# EnvironmentMonitorV5_1.net
KiCad netlist of a schematic drawn in EAGLE
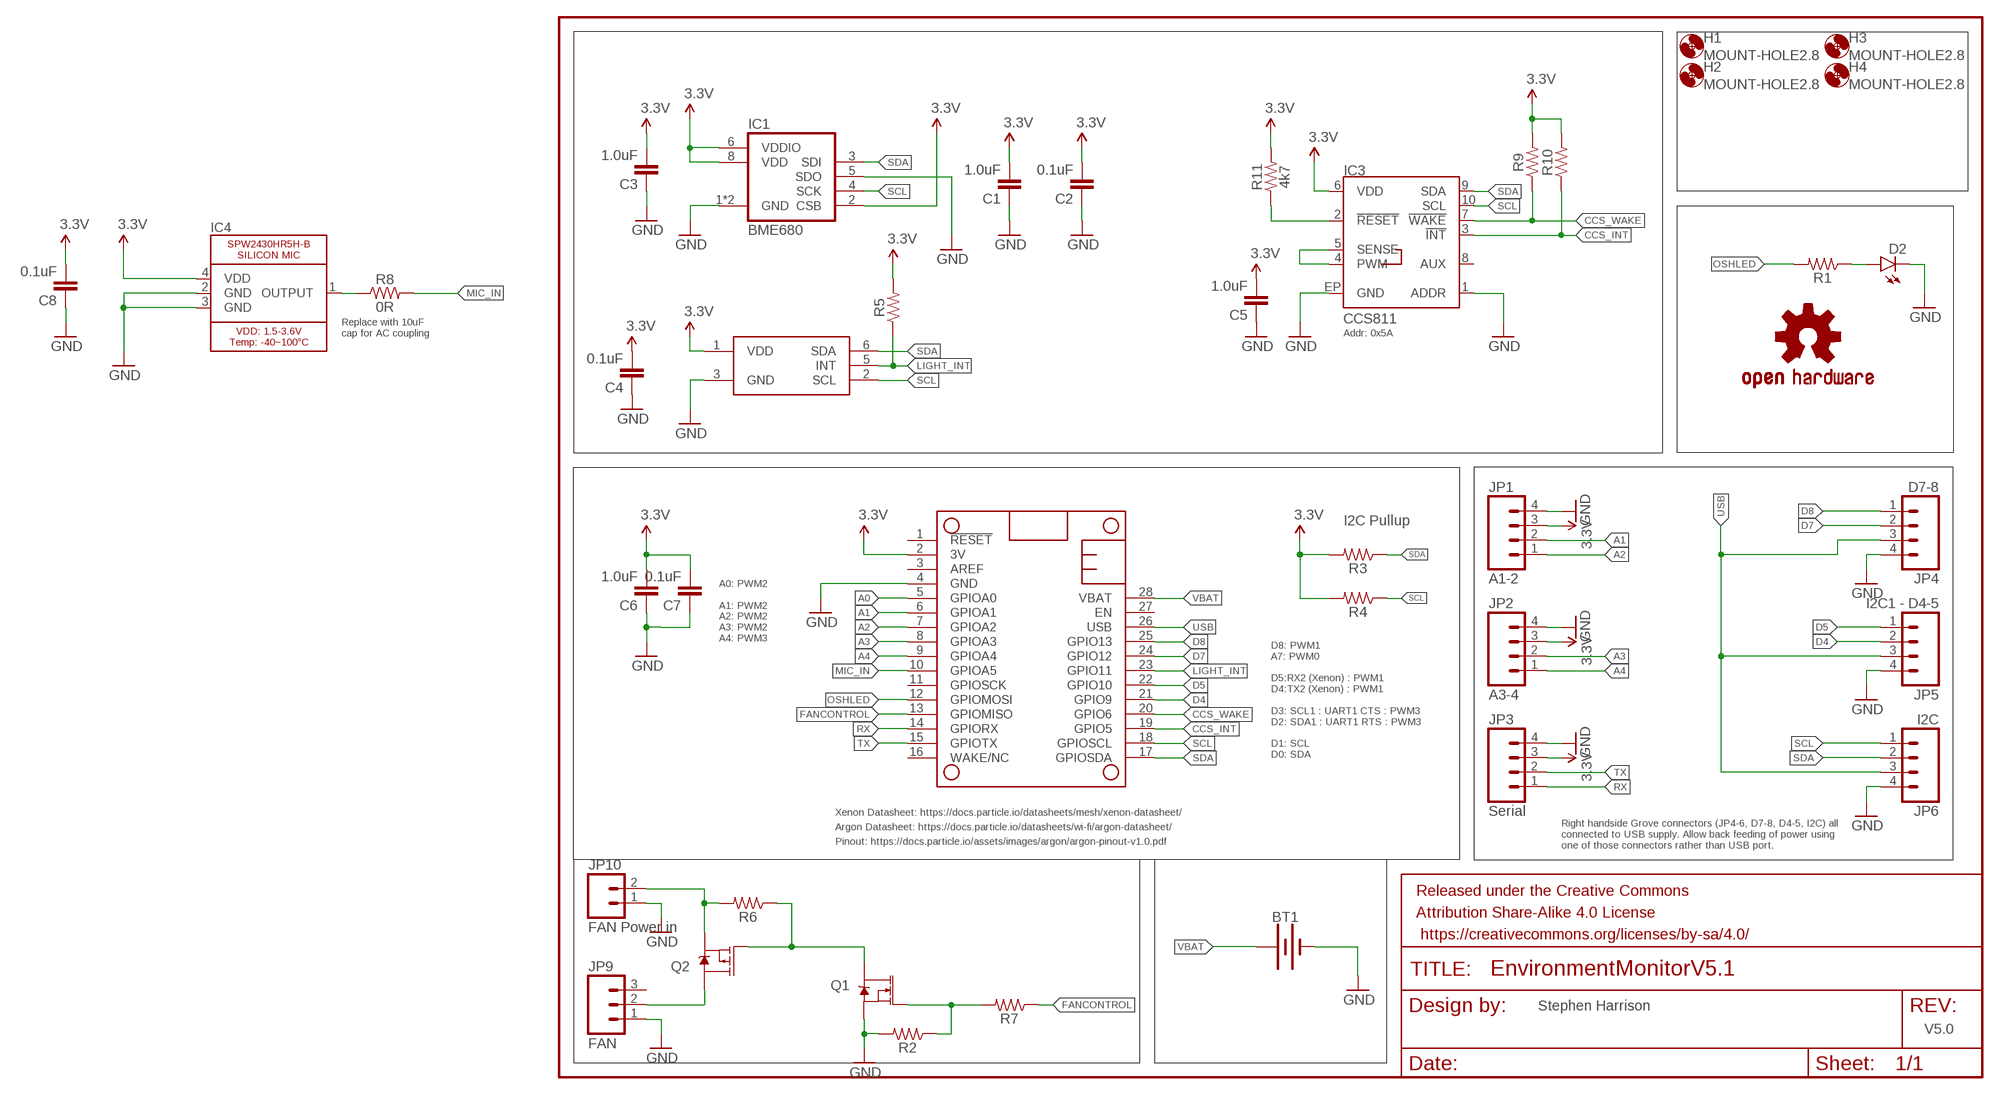
[diagram p0: schematic, sheet 1]

(export (version "E")
  (design (tool "Eeschema 10.0.6"))
  (components
    (comp (ref "BT1")
      (value "BATTERY-16340")
      (footprint "eagle-import:BATTERY_16340-HOLDER")
      (libsource (lib "eagle-import") (part "BATTERY-16340"))
    )
    (comp (ref "C1")
      (value "1.0uF")
      (footprint "eagle-import:0805-CAP")
      (libsource (lib "eagle-import") (part "1.0UF-25V-+80/-20(0805){dblquote}"))
    )
    (comp (ref "C2")
      (value "0.1uF")
      (footprint "eagle-import:0805-CAP")
      (libsource (lib "eagle-import") (part "1.0UF-25V-+80/-20(0805){dblquote}"))
    )
    (comp (ref "C3")
      (value "1.0uF")
      (footprint "eagle-import:0805-CAP")
      (libsource (lib "eagle-import") (part "1.0UF-25V-+80/-20(0805){dblquote}"))
    )
    (comp (ref "C4")
      (value "0.1uF")
      (footprint "eagle-import:0805-CAP")
      (libsource (lib "eagle-import") (part "1.0UF-25V-+80/-20(0805){dblquote}"))
    )
    (comp (ref "C5")
      (value "1.0uF")
      (footprint "eagle-import:0805-CAP")
      (libsource (lib "eagle-import") (part "1.0UF-25V-+80/-20(0805){dblquote}"))
    )
    (comp (ref "C6")
      (value "1.0uF")
      (footprint "eagle-import:0805-CAP")
      (libsource (lib "eagle-import") (part "1.0UF-25V-+80/-20(0805){dblquote}"))
    )
    (comp (ref "C7")
      (value "0.1uF")
      (footprint "eagle-import:0805-CAP")
      (libsource (lib "eagle-import") (part "1.0UF-25V-+80/-20(0805){dblquote}"))
    )
    (comp (ref "C8")
      (value "0.1uF")
      (footprint "eagle-import:0805-CAP")
      (libsource (lib "eagle-import") (part "1.0UF-25V-+80/-20(0805){dblquote}"))
    )
    (comp (ref "D2")
      (value "LED1206-BOTTOM")
      (footprint "eagle-import:LED-1206-BOTTOM")
      (libsource (lib "eagle-import") (part "LED1206-BOTTOM"))
    )
    (comp (ref "FRAME1")
      (value "FRAME-LETTER")
      (footprint "eagle-import:CREATIVE_COMMONS")
      (libsource (lib "eagle-import") (part "FRAME-LETTER"))
    )
    (comp (ref "H1")
      (value "MOUNT-HOLE2.8")
      (footprint "eagle-import:2,8")
      (libsource (lib "eagle-import") (part "MOUNT-HOLE2.8"))
    )
    (comp (ref "H2")
      (value "MOUNT-HOLE2.8")
      (footprint "eagle-import:2,8")
      (libsource (lib "eagle-import") (part "MOUNT-HOLE2.8"))
    )
    (comp (ref "H3")
      (value "MOUNT-HOLE2.8")
      (footprint "eagle-import:2,8")
      (libsource (lib "eagle-import") (part "MOUNT-HOLE2.8"))
    )
    (comp (ref "H4")
      (value "MOUNT-HOLE2.8")
      (footprint "eagle-import:2,8")
      (libsource (lib "eagle-import") (part "MOUNT-HOLE2.8"))
    )
    (comp (ref "IC1")
      (value "BME680")
      (footprint "eagle-import:BME680")
      (libsource (lib "eagle-import") (part "BME680"))
    )
    (comp (ref "IC2")
      (value "TCS3472")
      (footprint "eagle-import:FN-6")
      (libsource (lib "eagle-import") (part "TCS3472"))
    )
    (comp (ref "IC3")
      (value "CCS811")
      (footprint "eagle-import:LGA10")
      (libsource (lib "eagle-import") (part "CCS811"))
    )
    (comp (ref "IC4")
      (value "SPW2430HR5H-B")
      (footprint "eagle-import:SPW2430HR5H-B")
      (libsource (lib "eagle-import") (part "SPW2430HR5H-B"))
    )
    (comp (ref "IC5")
      (value "FEATHERWING_NODIM")
      (footprint "eagle-import:FEATHERWING_DIM")
      (libsource (lib "eagle-import") (part "FEATHERWING_NODIM"))
    )
    (comp (ref "JP1")
      (value "A1-2")
      (footprint "eagle-import:JST-4-PTH-VERT")
      (libsource (lib "eagle-import") (part "M04JST-PTH-VERT"))
    )
    (comp (ref "JP2")
      (value "A3-4")
      (footprint "eagle-import:JST-4-PTH-VERT")
      (libsource (lib "eagle-import") (part "M04JST-PTH-VERT"))
    )
    (comp (ref "JP3")
      (value "Serial")
      (footprint "eagle-import:JST-4-PTH-VERT")
      (libsource (lib "eagle-import") (part "M04JST-PTH-VERT"))
    )
    (comp (ref "JP4")
      (value "D7-8")
      (footprint "eagle-import:JST-4-PTH-VERT")
      (libsource (lib "eagle-import") (part "M04JST-PTH-VERT"))
    )
    (comp (ref "JP5")
      (value "I2C1 - D4-5")
      (footprint "eagle-import:JST-4-PTH-VERT")
      (libsource (lib "eagle-import") (part "M04JST-PTH-VERT"))
    )
    (comp (ref "JP6")
      (value "I2C")
      (footprint "eagle-import:JST-4-PTH-VERT")
      (libsource (lib "eagle-import") (part "M04JST-PTH-VERT"))
    )
    (comp (ref "JP9")
      (value "FAN")
      (footprint "eagle-import:MOLEX-1X3")
      (libsource (lib "eagle-import") (part "M03POLAR"))
    )
    (comp (ref "JP10")
      (value "FAN Power in")
      (footprint "eagle-import:MOLEX-1X2_LOCK")
      (libsource (lib "eagle-import") (part "M02POLAR_LOCK"))
    )
    (comp (ref "LOGO1")
      (value "OSHW-LOGOM")
      (footprint "eagle-import:OSHW-LOGO-M")
      (libsource (lib "eagle-import") (part "OSHW-LOGOM"))
    )
    (comp (ref "Q1")
      (value "220mA/50V/3.5Ω")
      (footprint "eagle-import:SOT23-3")
      (libsource (lib "eagle-import") (part "MOSFET-NCH-BSS138"))
    )
    (comp (ref "Q2")
      (value "4.3A/20V/54mΩ")
      (footprint "eagle-import:SOT23-3")
      (libsource (lib "eagle-import") (part "MOSFET_PCH-IRLML2244"))
    )
    (comp (ref "R1")
      (value "RESISTOR0805")
      (footprint "eagle-import:0805")
      (libsource (lib "eagle-import") (part "RESISTOR0805"))
    )
    (comp (ref "R2")
      (value "RESISTOR0805")
      (footprint "eagle-import:0805")
      (libsource (lib "eagle-import") (part "RESISTOR0805"))
    )
    (comp (ref "R3")
      (value "RESISTOR0805")
      (footprint "eagle-import:0805")
      (libsource (lib "eagle-import") (part "RESISTOR0805"))
    )
    (comp (ref "R4")
      (value "RESISTOR0805")
      (footprint "eagle-import:0805")
      (libsource (lib "eagle-import") (part "RESISTOR0805"))
    )
    (comp (ref "R5")
      (value "RESISTOR0805")
      (footprint "eagle-import:0805")
      (libsource (lib "eagle-import") (part "RESISTOR0805"))
    )
    (comp (ref "R6")
      (value "RESISTOR0805")
      (footprint "eagle-import:0805")
      (libsource (lib "eagle-import") (part "RESISTOR0805"))
    )
    (comp (ref "R7")
      (value "RESISTOR0805")
      (footprint "eagle-import:0805")
      (libsource (lib "eagle-import") (part "RESISTOR0805"))
    )
    (comp (ref "R8")
      (value "0R")
      (footprint "eagle-import:0805")
      (libsource (lib "eagle-import") (part "RESISTOR0805"))
    )
    (comp (ref "R9")
      (value "RESISTOR0805")
      (footprint "eagle-import:0805")
      (libsource (lib "eagle-import") (part "RESISTOR0805"))
    )
    (comp (ref "R10")
      (value "RESISTOR0805")
      (footprint "eagle-import:0805")
      (libsource (lib "eagle-import") (part "RESISTOR0805"))
    )
    (comp (ref "R11")
      (value "4k7")
      (footprint "eagle-import:0805")
      (libsource (lib "eagle-import") (part "RESISTOR0805"))
    )
  )
  (nets
    (net (code "1") (name "3.3V") (class "Default")
      (node (ref "C1") (pin "2") (pinfunction "2_2") (pintype "passive"))
      (node (ref "C2") (pin "2") (pinfunction "2_2") (pintype "passive"))
      (node (ref "C3") (pin "2") (pinfunction "2_2") (pintype "passive"))
      (node (ref "C4") (pin "2") (pinfunction "2_2") (pintype "passive"))
      (node (ref "C5") (pin "2") (pinfunction "2_2") (pintype "passive"))
      (node (ref "C6") (pin "2") (pinfunction "2_2") (pintype "passive"))
      (node (ref "C7") (pin "2") (pinfunction "2_2") (pintype "passive"))
      (node (ref "C8") (pin "2") (pinfunction "2_2") (pintype "passive"))
      (node (ref "IC1") (pin "2") (pinfunction "CSB_2") (pintype "input"))
      (node (ref "IC1") (pin "6") (pinfunction "VDDIO_6") (pintype "power_in"))
      (node (ref "IC1") (pin "8") (pinfunction "VDD_8") (pintype "power_in"))
      (node (ref "IC2") (pin "1") (pinfunction "VDD_1") (pintype "bidirectional"))
      (node (ref "IC3") (pin "6") (pinfunction "VDD_6") (pintype "bidirectional"))
      (node (ref "IC4") (pin "4") (pinfunction "VDD_4") (pintype "power_in"))
      (node (ref "IC5") (pin "2") (pinfunction "3V_2") (pintype "power_in"))
      (node (ref "JP1") (pin "3") (pinfunction "3_3") (pintype "passive"))
      (node (ref "JP2") (pin "3") (pinfunction "3_3") (pintype "passive"))
      (node (ref "JP3") (pin "3") (pinfunction "3_3") (pintype "passive"))
      (node (ref "R10") (pin "2") (pinfunction "2_2") (pintype "passive"))
      (node (ref "R11") (pin "2") (pinfunction "2_2") (pintype "passive"))
      (node (ref "R3") (pin "2") (pinfunction "2_2") (pintype "passive"))
      (node (ref "R4") (pin "2") (pinfunction "2_2") (pintype "passive"))
      (node (ref "R5") (pin "2") (pinfunction "2_2") (pintype "passive"))
      (node (ref "R9") (pin "2") (pinfunction "2_2") (pintype "passive"))
    )
    (net (code "2") (name "A0") (class "Default")
      (node (ref "IC5") (pin "5") (pinfunction "GPIOA0_5") (pintype "bidirectional"))
    )
    (net (code "3") (name "A1") (class "Default")
      (node (ref "IC5") (pin "6") (pinfunction "GPIOA1_6") (pintype "bidirectional"))
      (node (ref "JP1") (pin "2") (pinfunction "2_2") (pintype "passive"))
    )
    (net (code "4") (name "A2") (class "Default")
      (node (ref "IC5") (pin "7") (pinfunction "GPIOA2_7") (pintype "bidirectional"))
      (node (ref "JP1") (pin "1") (pinfunction "1_1") (pintype "passive"))
    )
    (net (code "5") (name "A3") (class "Default")
      (node (ref "IC5") (pin "8") (pinfunction "GPIOA3_8") (pintype "bidirectional"))
      (node (ref "JP2") (pin "2") (pinfunction "2_2") (pintype "passive"))
    )
    (net (code "6") (name "A4") (class "Default")
      (node (ref "IC5") (pin "9") (pinfunction "GPIOA4_9") (pintype "bidirectional"))
      (node (ref "JP2") (pin "1") (pinfunction "1_1") (pintype "passive"))
    )
    (net (code "7") (name "CCS_INT") (class "Default")
      (node (ref "IC3") (pin "3") (pinfunction "~{INT}_3") (pintype "bidirectional"))
      (node (ref "IC5") (pin "19") (pinfunction "GPIO5_19") (pintype "bidirectional"))
      (node (ref "R10") (pin "1") (pinfunction "1_1") (pintype "passive"))
    )
    (net (code "8") (name "CCS_WAKE") (class "Default")
      (node (ref "IC3") (pin "7") (pinfunction "~{WAKE}_7") (pintype "bidirectional"))
      (node (ref "IC5") (pin "20") (pinfunction "GPIO6_20") (pintype "bidirectional"))
      (node (ref "R9") (pin "1") (pinfunction "1_1") (pintype "passive"))
    )
    (net (code "9") (name "D4") (class "Default")
      (node (ref "IC5") (pin "21") (pinfunction "GPIO9_21") (pintype "bidirectional"))
      (node (ref "JP5") (pin "2") (pinfunction "2_2") (pintype "passive"))
    )
    (net (code "10") (name "D5") (class "Default")
      (node (ref "IC5") (pin "22") (pinfunction "GPIO10_22") (pintype "bidirectional"))
      (node (ref "JP5") (pin "1") (pinfunction "1_1") (pintype "passive"))
    )
    (net (code "11") (name "D7") (class "Default")
      (node (ref "IC5") (pin "24") (pinfunction "GPIO12_24") (pintype "bidirectional"))
      (node (ref "JP4") (pin "2") (pinfunction "2_2") (pintype "passive"))
    )
    (net (code "12") (name "D8") (class "Default")
      (node (ref "IC5") (pin "25") (pinfunction "GPIO13_25") (pintype "bidirectional"))
      (node (ref "JP4") (pin "1") (pinfunction "1_1") (pintype "passive"))
    )
    (net (code "13") (name "FANCONTROL") (class "Default")
      (node (ref "IC5") (pin "13") (pinfunction "GPIOMISO_13") (pintype "bidirectional"))
      (node (ref "R7") (pin "1") (pinfunction "1_1") (pintype "passive"))
    )
    (net (code "14") (name "GND") (class "Default")
      (node (ref "BT1") (pin "P$2") (pinfunction "-_P$2") (pintype "power_in"))
      (node (ref "C1") (pin "1") (pinfunction "1_1") (pintype "passive"))
      (node (ref "C2") (pin "1") (pinfunction "1_1") (pintype "passive"))
      (node (ref "C3") (pin "1") (pinfunction "1_1") (pintype "passive"))
      (node (ref "C4") (pin "1") (pinfunction "1_1") (pintype "passive"))
      (node (ref "C5") (pin "1") (pinfunction "1_1") (pintype "passive"))
      (node (ref "C6") (pin "1") (pinfunction "1_1") (pintype "passive"))
      (node (ref "C7") (pin "1") (pinfunction "1_1") (pintype "passive"))
      (node (ref "C8") (pin "1") (pinfunction "1_1") (pintype "passive"))
      (node (ref "D2") (pin "C") (pinfunction "C_C") (pintype "passive"))
      (node (ref "IC1") (pin "1") (pinfunction "GND_1") (pintype "power_in"))
      (node (ref "IC1") (pin "5") (pinfunction "SDO_5") (pintype "output"))
      (node (ref "IC1") (pin "7") (pinfunction "GND_7") (pintype "power_in"))
      (node (ref "IC2") (pin "3") (pinfunction "GND_3") (pintype "bidirectional"))
      (node (ref "IC3") (pin "1") (pinfunction "ADDR_1") (pintype "bidirectional"))
      (node (ref "IC3") (pin "EP") (pinfunction "GND_EP") (pintype "bidirectional"))
      (node (ref "IC4") (pin "2") (pinfunction "GND_2") (pintype "power_in"))
      (node (ref "IC4") (pin "3") (pinfunction "GND_3") (pintype "power_in"))
      (node (ref "IC5") (pin "4") (pinfunction "GND_4") (pintype "power_in"))
      (node (ref "JP1") (pin "4") (pinfunction "4_4") (pintype "passive"))
      (node (ref "JP10") (pin "1") (pinfunction "1_1") (pintype "passive"))
      (node (ref "JP2") (pin "4") (pinfunction "4_4") (pintype "passive"))
      (node (ref "JP3") (pin "4") (pinfunction "4_4") (pintype "passive"))
      (node (ref "JP4") (pin "4") (pinfunction "4_4") (pintype "passive"))
      (node (ref "JP5") (pin "4") (pinfunction "4_4") (pintype "passive"))
      (node (ref "JP6") (pin "4") (pinfunction "4_4") (pintype "passive"))
      (node (ref "JP9") (pin "1") (pinfunction "1_1") (pintype "passive"))
      (node (ref "Q1") (pin "2") (pinfunction "S_2") (pintype "bidirectional"))
      (node (ref "R2") (pin "2") (pinfunction "2_2") (pintype "passive"))
    )
    (net (code "15") (name "LIGHT_INT") (class "Default")
      (node (ref "IC2") (pin "5") (pinfunction "INT_5") (pintype "bidirectional"))
      (node (ref "IC5") (pin "23") (pinfunction "GPIO11_23") (pintype "bidirectional"))
      (node (ref "R5") (pin "1") (pinfunction "1_1") (pintype "passive"))
    )
    (net (code "16") (name "MIC_IN") (class "Default")
      (node (ref "IC5") (pin "10") (pinfunction "GPIOA5_10") (pintype "bidirectional"))
      (node (ref "R8") (pin "2") (pinfunction "2_2") (pintype "passive"))
    )
    (net (code "17") (name "Net-(D2-PadA)") (class "Default")
      (node (ref "D2") (pin "A") (pinfunction "A_A") (pintype "passive"))
      (node (ref "R1") (pin "1") (pinfunction "1_1") (pintype "passive"))
    )
    (net (code "18") (name "Net-(IC3-PWM)") (class "Default")
      (node (ref "IC3") (pin "4") (pinfunction "PWM_4") (pintype "bidirectional"))
      (node (ref "IC3") (pin "5") (pinfunction "SENSE_5") (pintype "bidirectional"))
    )
    (net (code "19") (name "Net-(IC3-~{RESET})") (class "Default")
      (node (ref "IC3") (pin "2") (pinfunction "~{RESET}_2") (pintype "bidirectional"))
      (node (ref "R11") (pin "1") (pinfunction "1_1") (pintype "passive"))
    )
    (net (code "20") (name "Net-(IC4-OUTPUT)") (class "Default")
      (node (ref "IC4") (pin "1") (pinfunction "OUTPUT_1") (pintype "output"))
      (node (ref "R8") (pin "1") (pinfunction "1_1") (pintype "passive"))
    )
    (net (code "21") (name "Net-(Q1-D)") (class "Default")
      (node (ref "Q1") (pin "3") (pinfunction "D_3") (pintype "bidirectional"))
      (node (ref "Q2") (pin "1") (pinfunction "G_1") (pintype "bidirectional"))
      (node (ref "R6") (pin "1") (pinfunction "1_1") (pintype "passive"))
    )
    (net (code "22") (name "Net-(Q1-G)") (class "Default")
      (node (ref "Q1") (pin "1") (pinfunction "G_1") (pintype "bidirectional"))
      (node (ref "R2") (pin "1") (pinfunction "1_1") (pintype "passive"))
      (node (ref "R7") (pin "2") (pinfunction "2_2") (pintype "passive"))
    )
    (net (code "23") (name "Net-(Q2-D)") (class "Default")
      (node (ref "JP9") (pin "2") (pinfunction "2_2") (pintype "passive"))
      (node (ref "Q2") (pin "3") (pinfunction "D_3") (pintype "bidirectional"))
    )
    (net (code "24") (name "Net-(Q2-S)") (class "Default")
      (node (ref "JP10") (pin "2") (pinfunction "2_2") (pintype "passive"))
      (node (ref "Q2") (pin "2") (pinfunction "S_2") (pintype "bidirectional"))
      (node (ref "R6") (pin "2") (pinfunction "2_2") (pintype "passive"))
    )
    (net (code "25") (name "OSHLED") (class "Default")
      (node (ref "IC5") (pin "12") (pinfunction "GPIOMOSI_12") (pintype "bidirectional"))
      (node (ref "R1") (pin "2") (pinfunction "2_2") (pintype "passive"))
    )
    (net (code "26") (name "RX") (class "Default")
      (node (ref "IC5") (pin "14") (pinfunction "GPIORX_14") (pintype "bidirectional"))
      (node (ref "JP3") (pin "1") (pinfunction "1_1") (pintype "passive"))
    )
    (net (code "27") (name "SCL") (class "Default")
      (node (ref "IC1") (pin "4") (pinfunction "SCK_4") (pintype "input"))
      (node (ref "IC2") (pin "2") (pinfunction "SCL_2") (pintype "bidirectional"))
      (node (ref "IC3") (pin "10") (pinfunction "SCL_10") (pintype "bidirectional"))
      (node (ref "IC5") (pin "18") (pinfunction "GPIOSCL_18") (pintype "bidirectional"))
      (node (ref "JP6") (pin "1") (pinfunction "1_1") (pintype "passive"))
      (node (ref "R4") (pin "1") (pinfunction "1_1") (pintype "passive"))
    )
    (net (code "28") (name "SDA") (class "Default")
      (node (ref "IC1") (pin "3") (pinfunction "SDI_3") (pintype "input"))
      (node (ref "IC2") (pin "6") (pinfunction "SDA_6") (pintype "bidirectional"))
      (node (ref "IC3") (pin "9") (pinfunction "SDA_9") (pintype "bidirectional"))
      (node (ref "IC5") (pin "17") (pinfunction "GPIOSDA_17") (pintype "bidirectional"))
      (node (ref "JP6") (pin "2") (pinfunction "2_2") (pintype "passive"))
      (node (ref "R3") (pin "1") (pinfunction "1_1") (pintype "passive"))
    )
    (net (code "29") (name "TX") (class "Default")
      (node (ref "IC5") (pin "15") (pinfunction "GPIOTX_15") (pintype "bidirectional"))
      (node (ref "JP3") (pin "2") (pinfunction "2_2") (pintype "passive"))
    )
    (net (code "30") (name "USB") (class "Default")
      (node (ref "IC5") (pin "26") (pinfunction "USB_26") (pintype "power_in"))
      (node (ref "JP4") (pin "3") (pinfunction "3_3") (pintype "passive"))
      (node (ref "JP5") (pin "3") (pinfunction "3_3") (pintype "passive"))
      (node (ref "JP6") (pin "3") (pinfunction "3_3") (pintype "passive"))
    )
    (net (code "31") (name "VBAT") (class "Default")
      (node (ref "BT1") (pin "P$1") (pinfunction "+_P$1") (pintype "power_in"))
      (node (ref "IC5") (pin "28") (pinfunction "VBAT_28") (pintype "power_in"))
    )
    (net (code "32") (name "unconnected-(IC3-AUX-Pad8)") (class "Default")
      (node (ref "IC3") (pin "8") (pinfunction "AUX_8") (pintype "bidirectional"))
    )
    (net (code "33") (name "unconnected-(IC5-AREF-Pad3)") (class "Default")
      (node (ref "IC5") (pin "3") (pinfunction "AREF_3") (pintype "passive"))
    )
    (net (code "34") (name "unconnected-(IC5-EN-Pad27)") (class "Default")
      (node (ref "IC5") (pin "27") (pinfunction "EN_27") (pintype "passive"))
    )
    (net (code "35") (name "unconnected-(IC5-GPIOSCK-Pad11)") (class "Default")
      (node (ref "IC5") (pin "11") (pinfunction "GPIOSCK_11") (pintype "bidirectional"))
    )
    (net (code "36") (name "unconnected-(IC5-WAKE{slash}NC-Pad16)") (class "Default")
      (node (ref "IC5") (pin "16") (pinfunction "WAKE/NC_16") (pintype "passive"))
    )
    (net (code "37") (name "unconnected-(IC5-~{RESET}-Pad1)") (class "Default")
      (node (ref "IC5") (pin "1") (pinfunction "~{RESET}_1") (pintype "input"))
    )
    (net (code "38") (name "unconnected-(JP9-Pad3)") (class "Default")
      (node (ref "JP9") (pin "3") (pinfunction "3_3") (pintype "passive"))
    )
  )
)
